# light_theremin.net
KiCad netlist of a schematic drawn in EAGLE
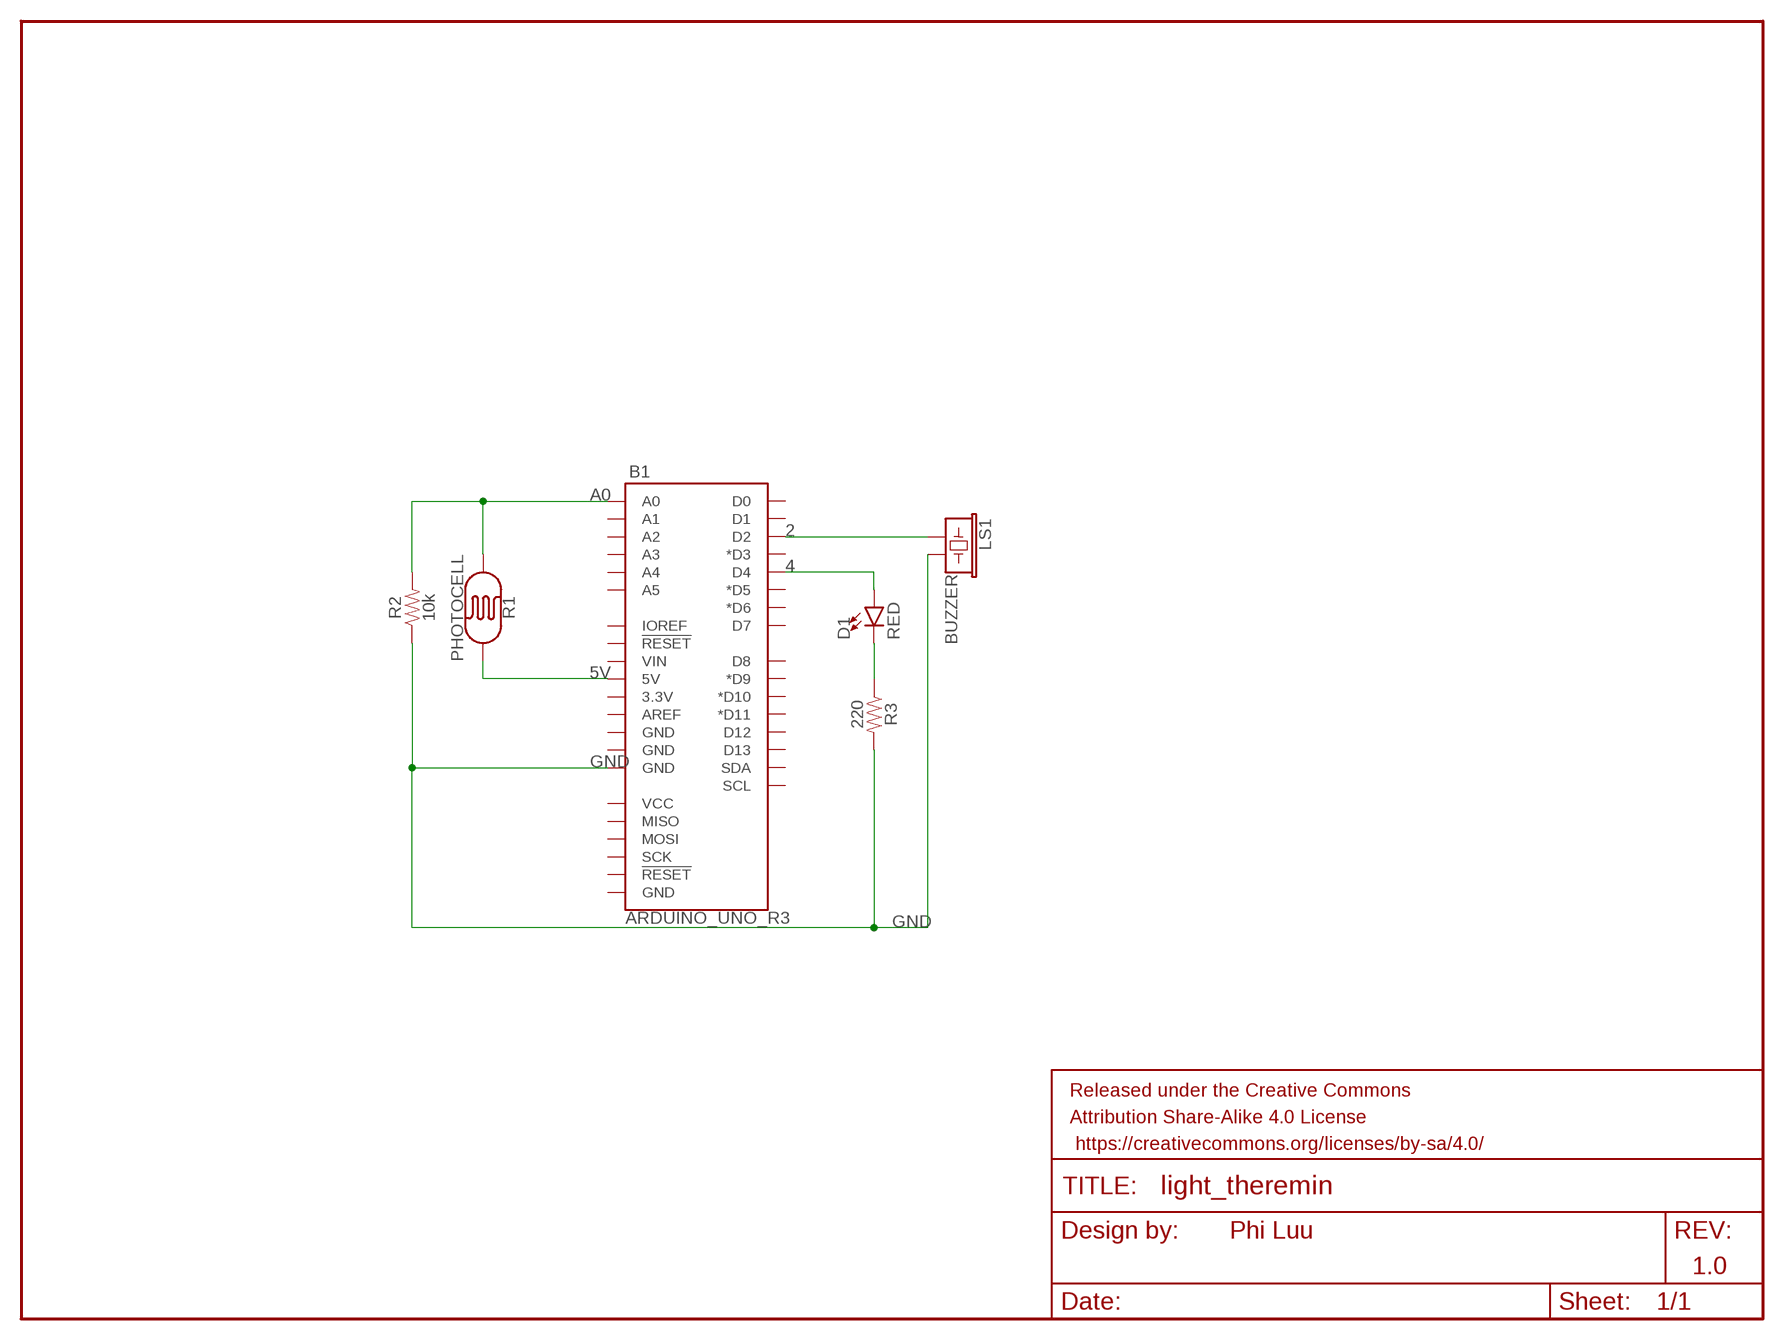
[diagram p0: schematic, sheet 1]

(export (version "E")
  (design (tool "Eeschema 10.0.6"))
  (components
    (comp (ref "B1")
      (value "ARDUINO_UNO_R3")
      (footprint "eagle-import:ARDUINO_R3")
      (libsource (lib "eagle-import") (part "ARDUINO_UNO_R3"))
    )
    (comp (ref "D1")
      (value "RED")
      (footprint "eagle-import:LED_5MM")
      (libsource (lib "eagle-import") (part "LED5MM"))
    )
    (comp (ref "FRAME1")
      (value "FRAME-LETTER")
      (footprint "eagle-import:CREATIVE_COMMONS")
      (libsource (lib "eagle-import") (part "FRAME-LETTER"))
    )
    (comp (ref "LS1")
      (value "BUZZER")
      (footprint "eagle-import:BUZZER-12MM")
      (libsource (lib "eagle-import") (part "BUZZER-PTH"))
    )
    (comp (ref "R1")
      (value "PHOTOCELL")
      (footprint "eagle-import:PHOTOCELL")
      (libsource (lib "eagle-import") (part "PHOTOCELLPTH"))
    )
    (comp (ref "R2")
      (value "10k")
      (footprint "eagle-import:AXIAL-0.3")
      (libsource (lib "eagle-import") (part "10KOHM-HORIZ-1/4W-5%"))
    )
    (comp (ref "R3")
      (value "220")
      (footprint "eagle-import:AXIAL-0.3")
      (libsource (lib "eagle-import") (part "10KOHM-HORIZ-1/4W-5%"))
    )
  )
  (nets
    (net (code "1") (name "/2") (class "Default")
      (node (ref "B1") (pin "D2") (pinfunction "D2_D2") (pintype "bidirectional"))
      (node (ref "LS1") (pin "+") (pinfunction "1_+") (pintype "passive"))
    )
    (net (code "2") (name "/4") (class "Default")
      (node (ref "B1") (pin "D4") (pinfunction "D4_D4") (pintype "bidirectional"))
      (node (ref "D1") (pin "A") (pinfunction "A_A") (pintype "passive"))
    )
    (net (code "3") (name "/5V") (class "Default")
      (node (ref "B1") (pin "5V") (pinfunction "5V_5V") (pintype "bidirectional"))
      (node (ref "R1") (pin "2") (pinfunction "P$2_2") (pintype "bidirectional"))
    )
    (net (code "4") (name "/A0") (class "Default")
      (node (ref "B1") (pin "A0") (pinfunction "A0_A0") (pintype "bidirectional"))
      (node (ref "R1") (pin "1") (pinfunction "P$1_1") (pintype "bidirectional"))
      (node (ref "R2") (pin "P$2") (pinfunction "2_P$2") (pintype "passive"))
    )
    (net (code "5") (name "/GND") (class "Default")
      (node (ref "B1") (pin "GND@2") (pinfunction "GND_GND@2") (pintype "bidirectional"))
      (node (ref "LS1") (pin "-") (pinfunction "2_-") (pintype "passive"))
      (node (ref "R2") (pin "P$1") (pinfunction "1_P$1") (pintype "passive"))
      (node (ref "R3") (pin "P$2") (pinfunction "2_P$2") (pintype "passive"))
    )
    (net (code "6") (name "Net-(D1-C)") (class "Default")
      (node (ref "D1") (pin "K") (pinfunction "C_K") (pintype "passive"))
      (node (ref "R3") (pin "P$1") (pinfunction "1_P$1") (pintype "passive"))
    )
    (net (code "7") (name "unconnected-(B1-*D3-PadD3)") (class "Default")
      (node (ref "B1") (pin "D3") (pinfunction "*D3_D3") (pintype "bidirectional"))
    )
    (net (code "8") (name "unconnected-(B1-*D5-PadD5)") (class "Default")
      (node (ref "B1") (pin "D5") (pinfunction "*D5_D5") (pintype "bidirectional"))
    )
    (net (code "9") (name "unconnected-(B1-*D6-PadD6)") (class "Default")
      (node (ref "B1") (pin "D6") (pinfunction "*D6_D6") (pintype "bidirectional"))
    )
    (net (code "10") (name "unconnected-(B1-*D9-PadD9)") (class "Default")
      (node (ref "B1") (pin "D9") (pinfunction "*D9_D9") (pintype "bidirectional"))
    )
    (net (code "11") (name "unconnected-(B1-*D10-PadD10)") (class "Default")
      (node (ref "B1") (pin "D10") (pinfunction "*D10_D10") (pintype "bidirectional"))
    )
    (net (code "12") (name "unconnected-(B1-*D11-PadD11)") (class "Default")
      (node (ref "B1") (pin "D11") (pinfunction "*D11_D11") (pintype "bidirectional"))
    )
    (net (code "13") (name "unconnected-(B1-GND-PadGND@1)") (class "Default")
      (node (ref "B1") (pin "GND@1") (pinfunction "GND_GND@1") (pintype "bidirectional"))
    )
    (net (code "14") (name "unconnected-(B1-GND-PadGND@3)") (class "Default")
      (node (ref "B1") (pin "GND@3") (pinfunction "GND_GND@3") (pintype "bidirectional"))
    )
    (net (code "15") (name "unconnected-(B1-GND-PadGND@4)") (class "Default")
      (node (ref "B1") (pin "GND@4") (pinfunction "GND_GND@4") (pintype "bidirectional"))
    )
    (net (code "16") (name "unconnected-(B1-Pad3.3V)") (class "Default")
      (node (ref "B1") (pin "3.3V") (pinfunction "3.3V_3.3V") (pintype "bidirectional"))
    )
    (net (code "17") (name "unconnected-(B1-PadA1)") (class "Default")
      (node (ref "B1") (pin "A1") (pinfunction "A1_A1") (pintype "bidirectional"))
    )
    (net (code "18") (name "unconnected-(B1-PadA2)") (class "Default")
      (node (ref "B1") (pin "A2") (pinfunction "A2_A2") (pintype "bidirectional"))
    )
    (net (code "19") (name "unconnected-(B1-PadA3)") (class "Default")
      (node (ref "B1") (pin "A3") (pinfunction "A3_A3") (pintype "bidirectional"))
    )
    (net (code "20") (name "unconnected-(B1-PadA4)") (class "Default")
      (node (ref "B1") (pin "A4") (pinfunction "A4_A4") (pintype "bidirectional"))
    )
    (net (code "21") (name "unconnected-(B1-PadA5)") (class "Default")
      (node (ref "B1") (pin "A5") (pinfunction "A5_A5") (pintype "bidirectional"))
    )
    (net (code "22") (name "unconnected-(B1-PadAREF)") (class "Default")
      (node (ref "B1") (pin "AREF") (pinfunction "AREF_AREF") (pintype "bidirectional"))
    )
    (net (code "23") (name "unconnected-(B1-PadD0)") (class "Default")
      (node (ref "B1") (pin "D0") (pinfunction "D0_D0") (pintype "bidirectional"))
    )
    (net (code "24") (name "unconnected-(B1-PadD1)") (class "Default")
      (node (ref "B1") (pin "D1") (pinfunction "D1_D1") (pintype "bidirectional"))
    )
    (net (code "25") (name "unconnected-(B1-PadD7)") (class "Default")
      (node (ref "B1") (pin "D7") (pinfunction "D7_D7") (pintype "bidirectional"))
    )
    (net (code "26") (name "unconnected-(B1-PadD8)") (class "Default")
      (node (ref "B1") (pin "D8") (pinfunction "D8_D8") (pintype "bidirectional"))
    )
    (net (code "27") (name "unconnected-(B1-PadD12)") (class "Default")
      (node (ref "B1") (pin "D12") (pinfunction "D12_D12") (pintype "bidirectional"))
    )
    (net (code "28") (name "unconnected-(B1-PadD13)") (class "Default")
      (node (ref "B1") (pin "D13") (pinfunction "D13_D13") (pintype "bidirectional"))
    )
    (net (code "29") (name "unconnected-(B1-PadIOREF)") (class "Default")
      (node (ref "B1") (pin "IOREF") (pinfunction "IOREF_IOREF") (pintype "bidirectional"))
    )
    (net (code "30") (name "unconnected-(B1-PadMISO)") (class "Default")
      (node (ref "B1") (pin "MISO") (pinfunction "MISO_MISO") (pintype "bidirectional"))
    )
    (net (code "31") (name "unconnected-(B1-PadMOSI)") (class "Default")
      (node (ref "B1") (pin "MOSI") (pinfunction "MOSI_MOSI") (pintype "bidirectional"))
    )
    (net (code "32") (name "unconnected-(B1-PadSCK)") (class "Default")
      (node (ref "B1") (pin "SCK") (pinfunction "SCK_SCK") (pintype "bidirectional"))
    )
    (net (code "33") (name "unconnected-(B1-PadSCL)") (class "Default")
      (node (ref "B1") (pin "SCL") (pinfunction "SCL_SCL") (pintype "bidirectional"))
    )
    (net (code "34") (name "unconnected-(B1-PadSDA)") (class "Default")
      (node (ref "B1") (pin "SDA") (pinfunction "SDA_SDA") (pintype "bidirectional"))
    )
    (net (code "35") (name "unconnected-(B1-PadVCC)") (class "Default")
      (node (ref "B1") (pin "VCC") (pinfunction "VCC_VCC") (pintype "bidirectional"))
    )
    (net (code "36") (name "unconnected-(B1-PadVIN)") (class "Default")
      (node (ref "B1") (pin "VIN") (pinfunction "VIN_VIN") (pintype "bidirectional"))
    )
    (net (code "37") (name "unconnected-(B1-~{RESET}-PadRESET@1)") (class "Default")
      (node (ref "B1") (pin "RESET@1") (pinfunction "~{RESET}_RESET@1") (pintype "bidirectional"))
    )
    (net (code "38") (name "unconnected-(B1-~{RESET}-PadRESET@2)") (class "Default")
      (node (ref "B1") (pin "RESET@2") (pinfunction "~{RESET}_RESET@2") (pintype "bidirectional"))
    )
  )
)
